# inktime.net
KiCad netlist of a schematic drawn in EAGLE
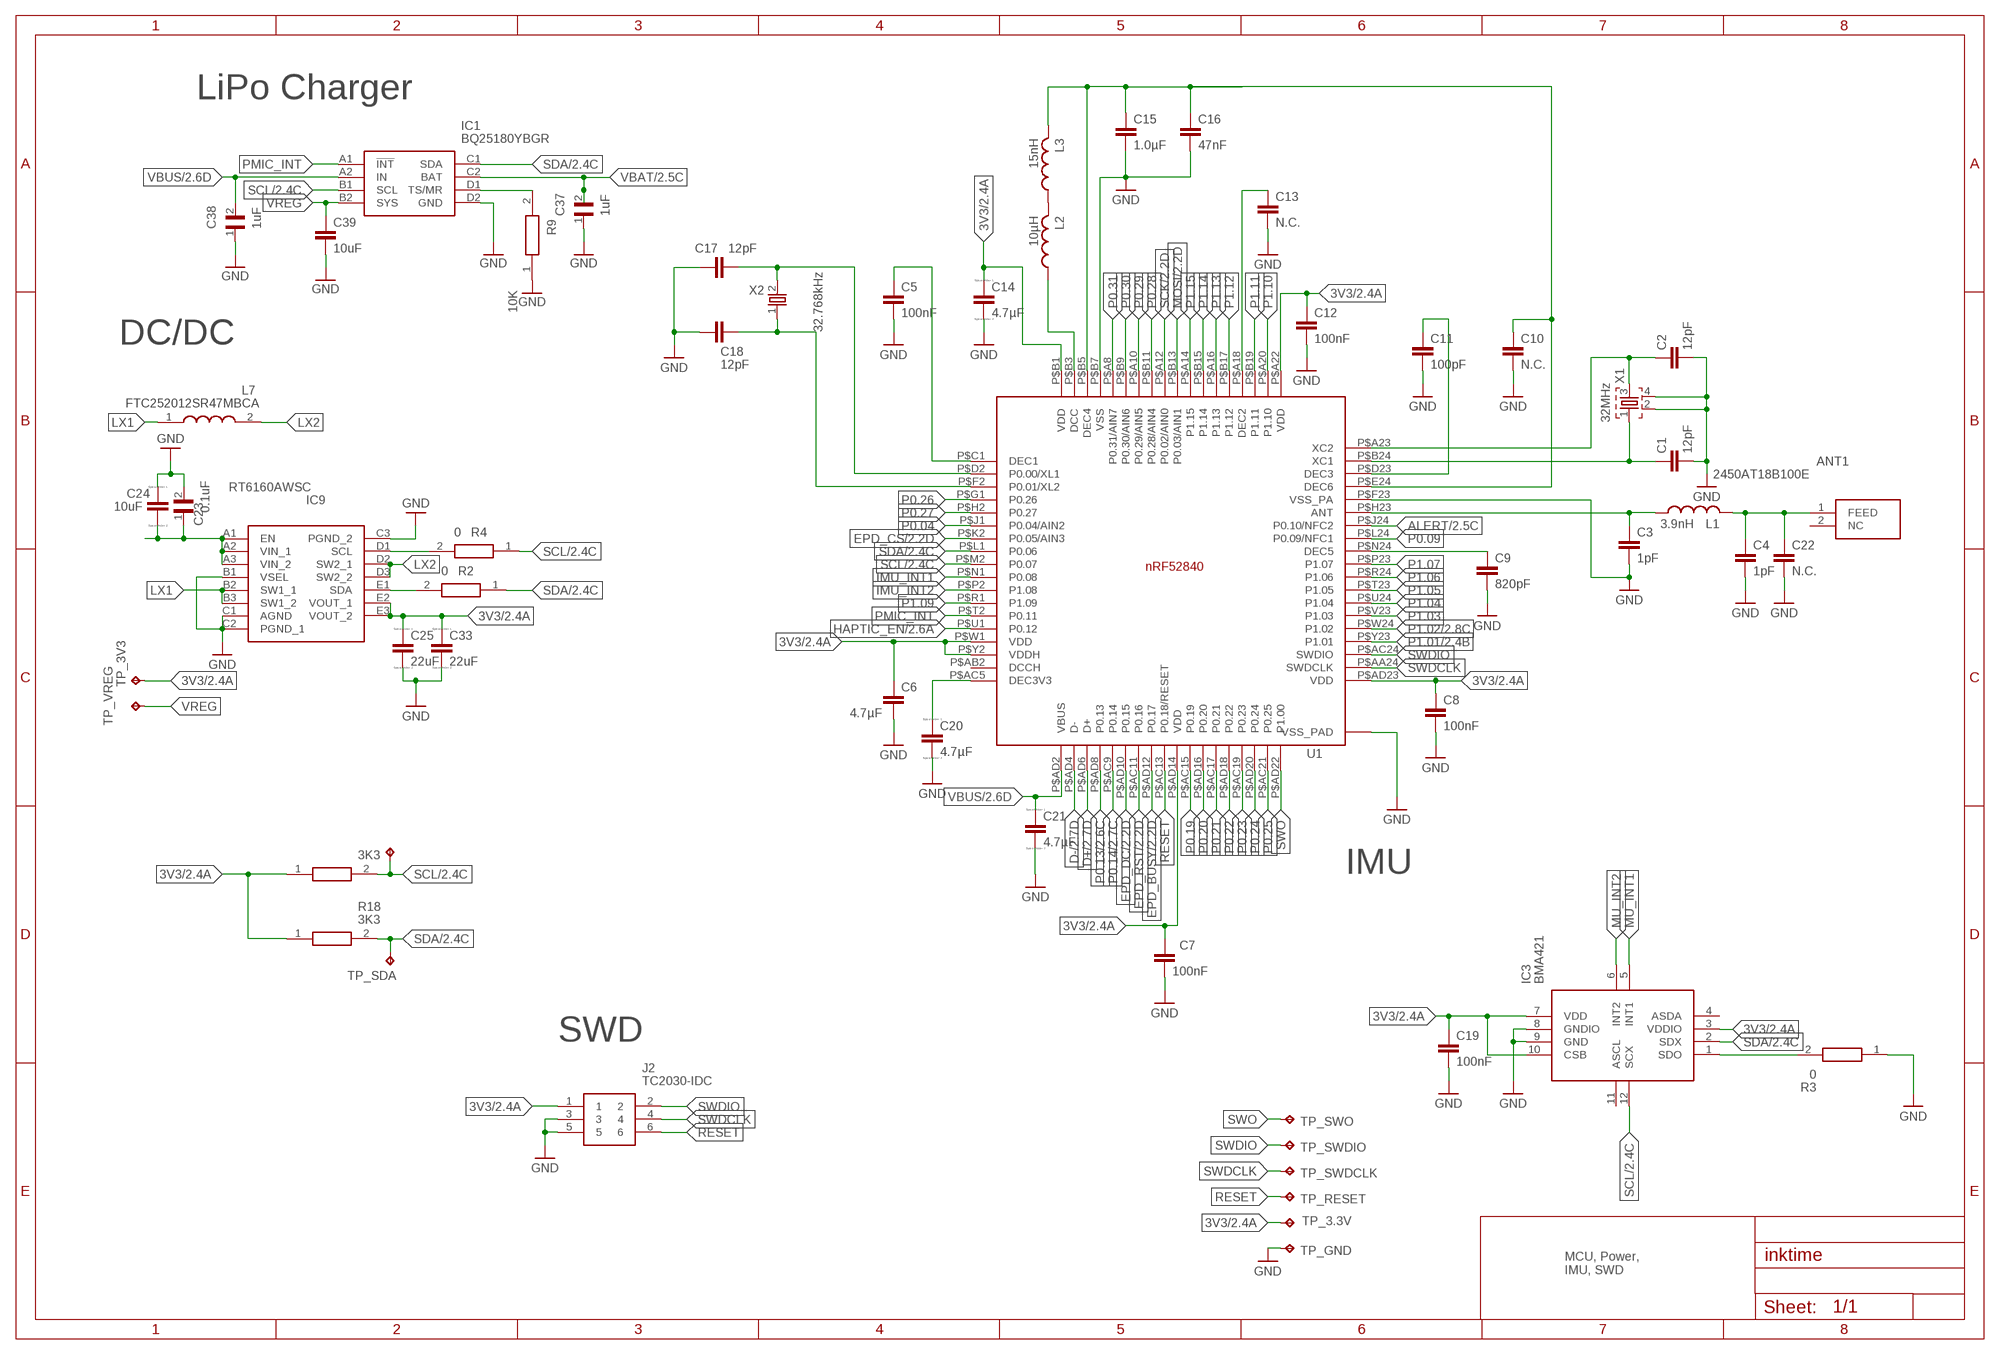
[diagram p0: schematic, sheet 1, part 1 of 2]
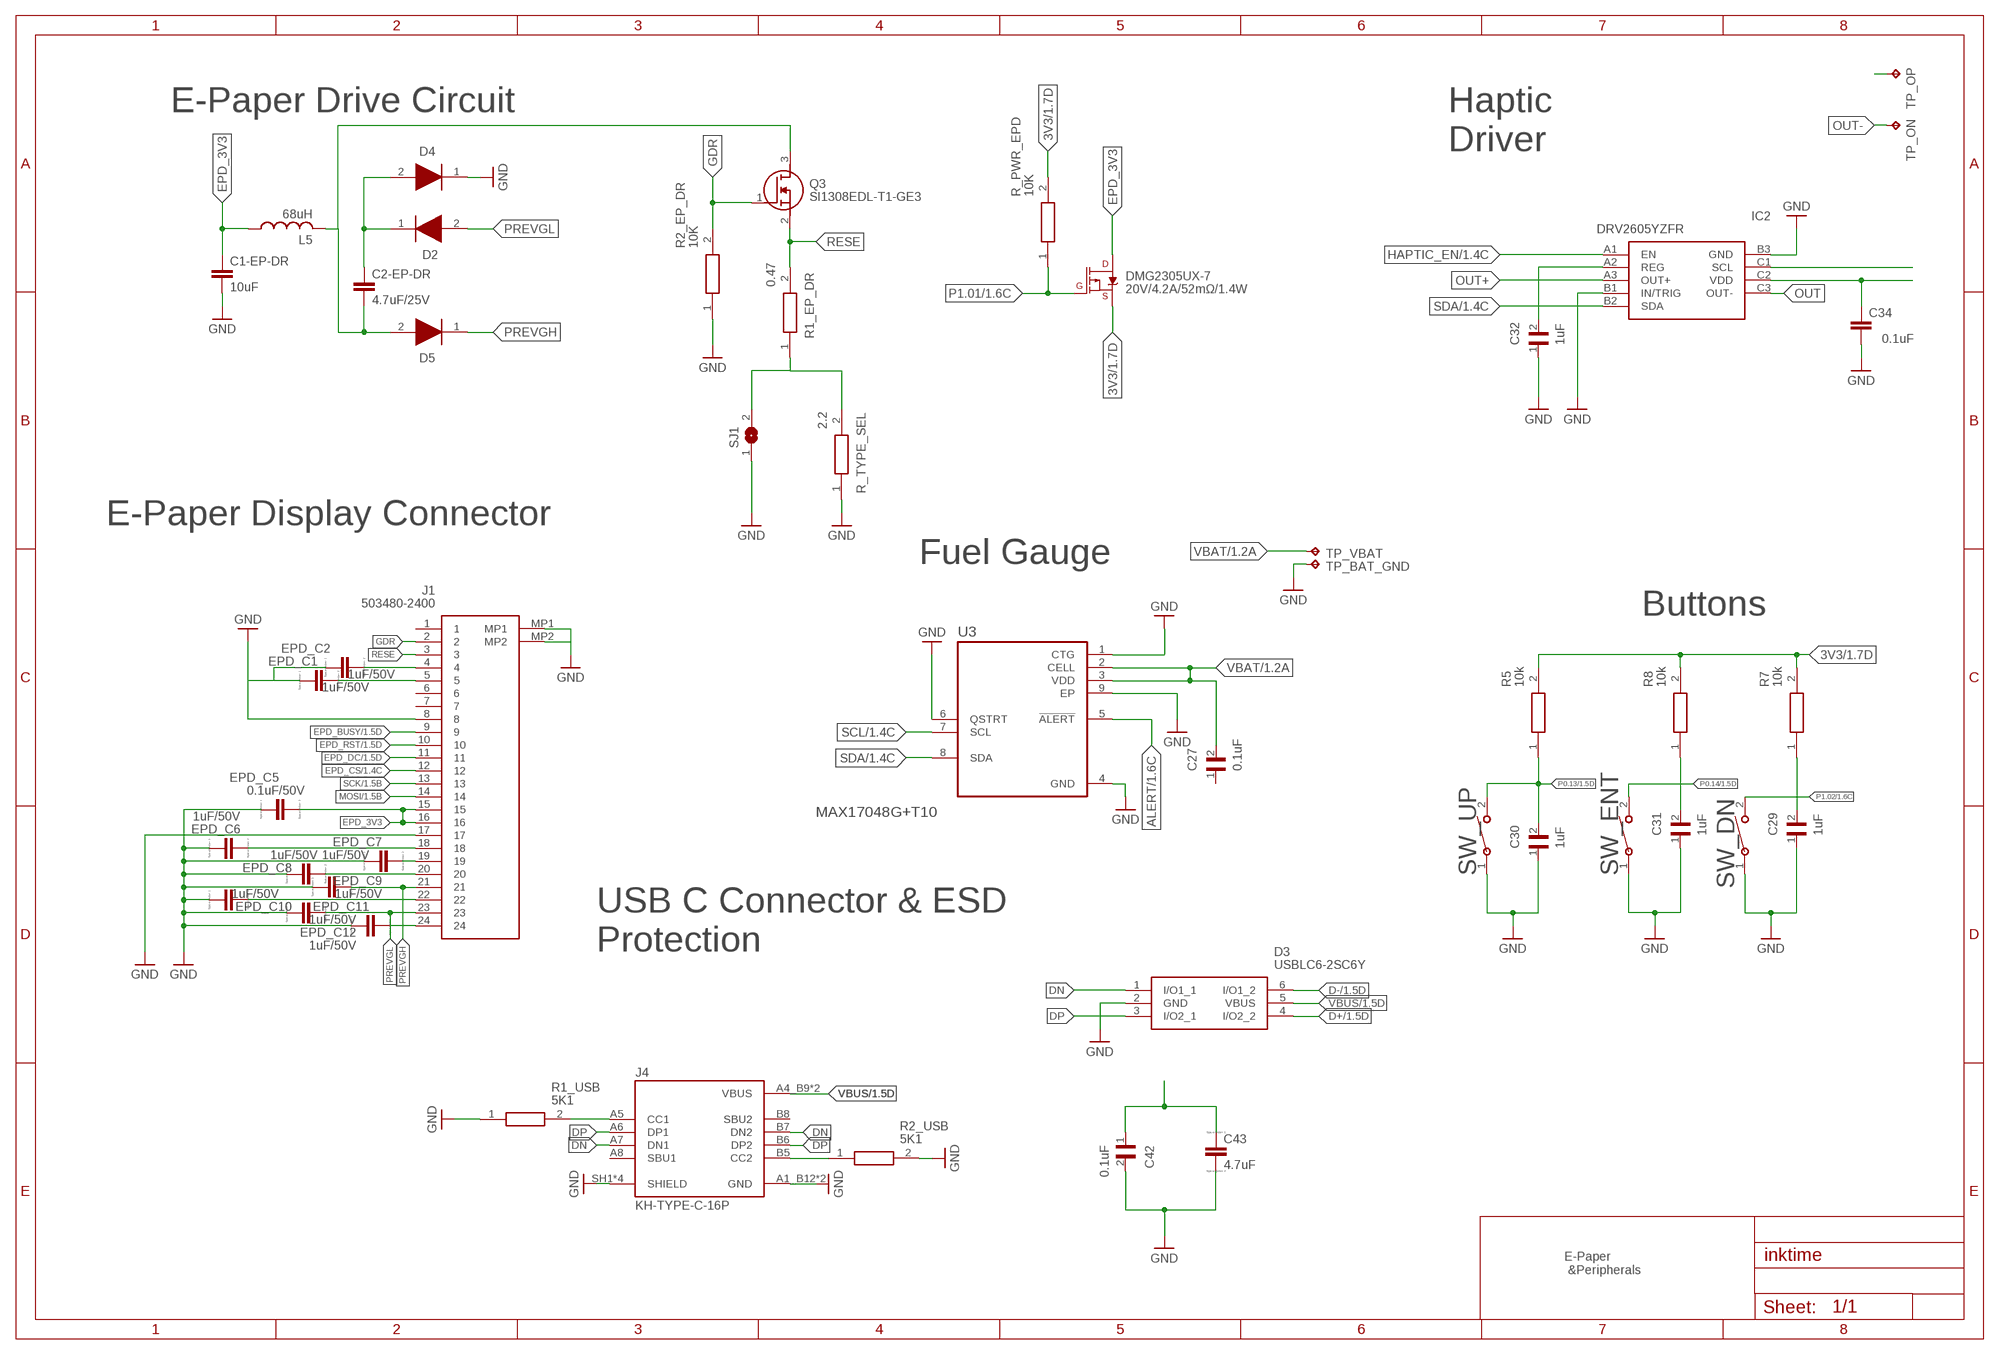
[diagram p1: schematic, sheet 1, part 2 of 2]

(export (version "E")
  (design (tool "Eeschema 10.0.6"))
  (components
    (comp (ref "ANT1")
      (value "2450AT18B100E")
      (footprint "eagle-import:2450AT18B100E_ANTC3216X140N")
      (fields (field (name "MOUSER_PART_NUMBER") "609-2450AT18B100E"))
      (libsource (lib "eagle-import") (part "2450AT18B100E_2450AT18B100E"))
    )
    (comp (ref "C1")
      (value "12pF")
      (footprint "eagle-import:NORDIC_NRF_3_RESC0201_L")
      (libsource (lib "eagle-import") (part "NORDIC_NRF_3_CAPACITOR_0201_L"))
    )
    (comp (ref "C1-EP-DR")
      (value "10uF")
      (footprint "eagle-import:NORDIC_NRF_3_RESC0201_L")
      (libsource (lib "eagle-import") (part "NORDIC_NRF_3_CAPACITOR_0201_L"))
    )
    (comp (ref "C2")
      (value "12pF")
      (footprint "eagle-import:NORDIC_NRF_3_RESC0201_L")
      (libsource (lib "eagle-import") (part "NORDIC_NRF_3_CAPACITOR_0201_L"))
    )
    (comp (ref "C2-EP-DR")
      (value "4.7uF/25V")
      (footprint "eagle-import:NORDIC_NRF_3_RESC0201_L")
      (libsource (lib "eagle-import") (part "NORDIC_NRF_3_CAPACITOR_0201_L"))
    )
    (comp (ref "C3")
      (value "1pF")
      (footprint "eagle-import:NORDIC_NRF_3_RESC0201_L")
      (libsource (lib "eagle-import") (part "NORDIC_NRF_3_CAPACITOR_0201_L"))
    )
    (comp (ref "C4")
      (value "1pF")
      (footprint "eagle-import:NORDIC_NRF_3_RESC0201_L")
      (libsource (lib "eagle-import") (part "NORDIC_NRF_3_CAPACITOR_0201_L"))
    )
    (comp (ref "C5")
      (value "100nF")
      (footprint "eagle-import:NORDIC_NRF_3_RESC0201_L")
      (libsource (lib "eagle-import") (part "NORDIC_NRF_3_CAPACITOR_0201_L"))
    )
    (comp (ref "C6")
      (value "4.7µF")
      (footprint "eagle-import:NORDIC_NRF_3_RESC0201_L")
      (libsource (lib "eagle-import") (part "NORDIC_NRF_3_CAPACITOR_0201_L"))
    )
    (comp (ref "C7")
      (value "100nF")
      (footprint "eagle-import:NORDIC_NRF_3_RESC0201_L")
      (libsource (lib "eagle-import") (part "NORDIC_NRF_3_CAPACITOR_0201_L"))
    )
    (comp (ref "C8")
      (value "100nF")
      (footprint "eagle-import:NORDIC_NRF_3_RESC0201_L")
      (libsource (lib "eagle-import") (part "NORDIC_NRF_3_CAPACITOR_0201_L"))
    )
    (comp (ref "C9")
      (value "820pF")
      (footprint "eagle-import:NORDIC_NRF_3_RESC0201_L")
      (libsource (lib "eagle-import") (part "NORDIC_NRF_3_CAPACITOR_0201_L"))
    )
    (comp (ref "C10")
      (value "N.C.")
      (footprint "eagle-import:NORDIC_NRF_3_RESC0201_L")
      (libsource (lib "eagle-import") (part "NORDIC_NRF_3_CAPACITOR_0201_L"))
    )
    (comp (ref "C11")
      (value "100pF")
      (footprint "eagle-import:NORDIC_NRF_3_RESC0201_L")
      (libsource (lib "eagle-import") (part "NORDIC_NRF_3_CAPACITOR_0201_L"))
    )
    (comp (ref "C12")
      (value "100nF")
      (footprint "eagle-import:NORDIC_NRF_3_RESC0201_L")
      (libsource (lib "eagle-import") (part "NORDIC_NRF_3_CAPACITOR_0201_L"))
    )
    (comp (ref "C13")
      (value "N.C.")
      (footprint "eagle-import:NORDIC_NRF_3_RESC0201_L")
      (libsource (lib "eagle-import") (part "NORDIC_NRF_3_CAPACITOR_0201_L"))
    )
    (comp (ref "C14")
      (value "4.7µF")
      (footprint "eagle-import:ESP32_C6_LIBRARY_1_ESP32_WROVER_EAGLE-LTSPICE_C0402")
      (libsource (lib "eagle-import") (part "ESP32_C6_LIBRARY_1_ESP32_WROVER_EAGLE-LTSPICE_CC0402"))
    )
    (comp (ref "C15")
      (value "1.0µF")
      (footprint "eagle-import:NORDIC_NRF_3_RESC0201_L")
      (libsource (lib "eagle-import") (part "NORDIC_NRF_3_CAPACITOR_0201_L"))
    )
    (comp (ref "C16")
      (value "47nF")
      (footprint "eagle-import:NORDIC_NRF_3_RESC0201_L")
      (libsource (lib "eagle-import") (part "NORDIC_NRF_3_CAPACITOR_0201_L"))
    )
    (comp (ref "C17")
      (value "12pF")
      (footprint "eagle-import:NORDIC_NRF_3_RESC0201_L")
      (libsource (lib "eagle-import") (part "NORDIC_NRF_3_CAPACITOR_0201_L"))
    )
    (comp (ref "C18")
      (value "12pF")
      (footprint "eagle-import:NORDIC_NRF_3_RESC0201_L")
      (libsource (lib "eagle-import") (part "NORDIC_NRF_3_CAPACITOR_0201_L"))
    )
    (comp (ref "C19")
      (value "100nF")
      (footprint "eagle-import:NORDIC_NRF_3_RESC0201_L")
      (libsource (lib "eagle-import") (part "NORDIC_NRF_3_CAPACITOR_0201_L"))
    )
    (comp (ref "C20")
      (value "4.7µF")
      (footprint "eagle-import:ESP32_C6_LIBRARY_1_ESP32_WROVER_EAGLE-LTSPICE_C0402")
      (libsource (lib "eagle-import") (part "ESP32_C6_LIBRARY_1_ESP32_WROVER_EAGLE-LTSPICE_CC0402"))
    )
    (comp (ref "C21")
      (value "4.7µF")
      (footprint "eagle-import:ESP32_C6_LIBRARY_1_ESP32_WROVER_EAGLE-LTSPICE_C0402")
      (libsource (lib "eagle-import") (part "ESP32_C6_LIBRARY_1_ESP32_WROVER_EAGLE-LTSPICE_CC0402"))
    )
    (comp (ref "C22")
      (value "N.C.")
      (footprint "eagle-import:NORDIC_NRF_3_RESC0201_L")
      (libsource (lib "eagle-import") (part "NORDIC_NRF_3_CAPACITOR_0201_L"))
    )
    (comp (ref "C23")
      (value "0.1uF")
      (footprint "eagle-import:GRM011R60J152KE01L_2_CAPC0201X13N")
      (fields (field (name "MF") "Murata") (field (name "MP") "GRM011R60J152KE01L"))
      (libsource (lib "eagle-import") (part "GRM011R60J152KE01L_2_GRM011R60J152KE01L"))
    )
    (comp (ref "C24")
      (value "10uF")
      (footprint "eagle-import:ESP32_C6_LIBRARY_1_ESP32_WROVER_EAGLE-LTSPICE_C0402")
      (libsource (lib "eagle-import") (part "ESP32_C6_LIBRARY_1_ESP32_WROVER_EAGLE-LTSPICE_CC0402"))
    )
    (comp (ref "C25")
      (value "22uF")
      (footprint "eagle-import:ESP32_C6_LIBRARY_1_ESP32_WROVER_EAGLE-LTSPICE_C0402")
      (libsource (lib "eagle-import") (part "ESP32_C6_LIBRARY_1_ESP32_WROVER_EAGLE-LTSPICE_CC0402"))
    )
    (comp (ref "C27")
      (value "0.1uF")
      (footprint "eagle-import:GRM011R60J152KE01L_2_CAPC0201X13N")
      (fields (field (name "MF") "Murata") (field (name "MP") "GRM011R60J152KE01L"))
      (libsource (lib "eagle-import") (part "GRM011R60J152KE01L_2_GRM011R60J152KE01L"))
    )
    (comp (ref "C29")
      (value "1uF")
      (footprint "eagle-import:GRM011R60J152KE01L_2_CAPC0201X13N")
      (fields (field (name "MF") "Murata") (field (name "MP") "GRM011R60J152KE01L"))
      (libsource (lib "eagle-import") (part "GRM011R60J152KE01L_2_GRM011R60J152KE01L"))
    )
    (comp (ref "C30")
      (value "1uF")
      (footprint "eagle-import:GRM011R60J152KE01L_2_CAPC0201X13N")
      (fields (field (name "MF") "Murata") (field (name "MP") "GRM011R60J152KE01L"))
      (libsource (lib "eagle-import") (part "GRM011R60J152KE01L_2_GRM011R60J152KE01L"))
    )
    (comp (ref "C31")
      (value "1uF")
      (footprint "eagle-import:GRM011R60J152KE01L_2_CAPC0201X13N")
      (fields (field (name "MF") "Murata") (field (name "MP") "GRM011R60J152KE01L"))
      (libsource (lib "eagle-import") (part "GRM011R60J152KE01L_2_GRM011R60J152KE01L"))
    )
    (comp (ref "C32")
      (value "1uF")
      (footprint "eagle-import:GRM011R60J152KE01L_2_CAPC0201X13N")
      (fields (field (name "MF") "Murata") (field (name "MP") "GRM011R60J152KE01L"))
      (libsource (lib "eagle-import") (part "GRM011R60J152KE01L_2_GRM011R60J152KE01L"))
    )
    (comp (ref "C33")
      (value "22uF")
      (footprint "eagle-import:ESP32_C6_LIBRARY_1_ESP32_WROVER_EAGLE-LTSPICE_C0402")
      (libsource (lib "eagle-import") (part "ESP32_C6_LIBRARY_1_ESP32_WROVER_EAGLE-LTSPICE_CC0402"))
    )
    (comp (ref "C34")
      (value "0.1uF")
      (footprint "eagle-import:NORDIC_NRF_3_RESC0201_L")
      (libsource (lib "eagle-import") (part "NORDIC_NRF_3_CAPACITOR_0201_L"))
    )
    (comp (ref "C37")
      (value "1uF")
      (footprint "eagle-import:GRM011R60J152KE01L_2_CAPC0201X13N")
      (fields (field (name "MF") "Murata") (field (name "MP") "GRM011R60J152KE01L"))
      (libsource (lib "eagle-import") (part "GRM011R60J152KE01L_2_GRM011R60J152KE01L"))
    )
    (comp (ref "C38")
      (value "1uF")
      (footprint "eagle-import:GRM011R60J152KE01L_2_CAPC0201X13N")
      (fields (field (name "MF") "Murata") (field (name "MP") "GRM011R60J152KE01L"))
      (libsource (lib "eagle-import") (part "GRM011R60J152KE01L_2_GRM011R60J152KE01L"))
    )
    (comp (ref "C39")
      (value "10uF")
      (footprint "eagle-import:NORDIC_NRF_3_RESC0201_L")
      (libsource (lib "eagle-import") (part "NORDIC_NRF_3_CAPACITOR_0201_L"))
    )
    (comp (ref "C42")
      (value "0.1uF")
      (footprint "eagle-import:GRM011R60J152KE01L_2_CAPC0201X13N")
      (fields (field (name "MF") "Murata") (field (name "MP") "GRM011R60J152KE01L"))
      (libsource (lib "eagle-import") (part "GRM011R60J152KE01L_2_GRM011R60J152KE01L"))
    )
    (comp (ref "C43")
      (value "4.7uF")
      (footprint "eagle-import:ESP32_C6_LIBRARY_1_ESP32_WROVER_EAGLE-LTSPICE_C0402")
      (libsource (lib "eagle-import") (part "ESP32_C6_LIBRARY_1_ESP32_WROVER_EAGLE-LTSPICE_CC0402"))
    )
    (comp (ref "D2")
      (value "ESP32_C6_LIBRARY_5_MBR0530")
      (footprint "eagle-import:ESP32_C6_LIBRARY_5_SOD3716X135N")
      (fields (field (name "MF") "ON Semiconductor") (field (name "MP") "MBR0530"))
      (libsource (lib "eagle-import") (part "ESP32_C6_LIBRARY_5_MBR0530"))
    )
    (comp (ref "D3")
      (value "USBLC6-2SC6Y")
      (footprint "eagle-import:ESP32_C6_LIBRARY_3_SOT95P280X145-6N")
      (fields (field (name "MF") "STMicroelectronics"))
      (libsource (lib "eagle-import") (part "ESP32_C6_LIBRARY_3_USBLC6-2SC6Y"))
    )
    (comp (ref "D4")
      (value "ESP32_C6_LIBRARY_5_MBR0530")
      (footprint "eagle-import:ESP32_C6_LIBRARY_5_SOD3716X135N")
      (fields (field (name "MF") "ON Semiconductor") (field (name "MP") "MBR0530"))
      (libsource (lib "eagle-import") (part "ESP32_C6_LIBRARY_5_MBR0530"))
    )
    (comp (ref "D5")
      (value "ESP32_C6_LIBRARY_5_MBR0530")
      (footprint "eagle-import:ESP32_C6_LIBRARY_5_SOD3716X135N")
      (fields (field (name "MF") "ON Semiconductor") (field (name "MP") "MBR0530"))
      (libsource (lib "eagle-import") (part "ESP32_C6_LIBRARY_5_MBR0530"))
    )
    (comp (ref "DMG2305UX-7")
      (value "20V/4.2A/52mΩ/1.4W")
      (footprint "eagle-import:ESP32_C6_LIBRARY_4_ESP32_C6_LIBRARY_4_ESP32_C6_LIBRARY_4_ESP32_C6_LIBRARY_4_ESP32_WROVER_SPARKFUN-DISCRETESEMI_SOT23-3")
      (libsource (lib "eagle-import") (part "ESP32_C6_LIBRARY_4_ESP32_WROVER_SPARKFUN-DISCRETESEMI_MOSFET_PCH-DMG2305UX-7"))
    )
    (comp (ref "EPD_C1")
      (value "1uF/50V")
      (footprint "eagle-import:ESP32_C6_LIBRARY_1_ESP32_WROVER_EAGLE-LTSPICE_C0402")
      (libsource (lib "eagle-import") (part "ESP32_C6_LIBRARY_1_ESP32_WROVER_EAGLE-LTSPICE_CC0402"))
    )
    (comp (ref "EPD_C2")
      (value "1uF/50V")
      (footprint "eagle-import:ESP32_C6_LIBRARY_1_ESP32_WROVER_EAGLE-LTSPICE_C0402")
      (libsource (lib "eagle-import") (part "ESP32_C6_LIBRARY_1_ESP32_WROVER_EAGLE-LTSPICE_CC0402"))
    )
    (comp (ref "EPD_C5")
      (value "0.1uF/50V")
      (footprint "eagle-import:ESP32_C6_LIBRARY_1_ESP32_WROVER_EAGLE-LTSPICE_C0402")
      (libsource (lib "eagle-import") (part "ESP32_C6_LIBRARY_1_ESP32_WROVER_EAGLE-LTSPICE_CC0402"))
    )
    (comp (ref "EPD_C6")
      (value "1uF/50V")
      (footprint "eagle-import:ESP32_C6_LIBRARY_1_ESP32_WROVER_EAGLE-LTSPICE_C0402")
      (libsource (lib "eagle-import") (part "ESP32_C6_LIBRARY_1_ESP32_WROVER_EAGLE-LTSPICE_CC0402"))
    )
    (comp (ref "EPD_C7")
      (value "1uF/50V")
      (footprint "eagle-import:ESP32_C6_LIBRARY_1_ESP32_WROVER_EAGLE-LTSPICE_C0402")
      (libsource (lib "eagle-import") (part "ESP32_C6_LIBRARY_1_ESP32_WROVER_EAGLE-LTSPICE_CC0402"))
    )
    (comp (ref "EPD_C8")
      (value "1uF/50V")
      (footprint "eagle-import:ESP32_C6_LIBRARY_1_ESP32_WROVER_EAGLE-LTSPICE_C0402")
      (libsource (lib "eagle-import") (part "ESP32_C6_LIBRARY_1_ESP32_WROVER_EAGLE-LTSPICE_CC0402"))
    )
    (comp (ref "EPD_C9")
      (value "1uF/50V")
      (footprint "eagle-import:ESP32_C6_LIBRARY_1_ESP32_WROVER_EAGLE-LTSPICE_C0402")
      (libsource (lib "eagle-import") (part "ESP32_C6_LIBRARY_1_ESP32_WROVER_EAGLE-LTSPICE_CC0402"))
    )
    (comp (ref "EPD_C10")
      (value "1uF/50V")
      (footprint "eagle-import:ESP32_C6_LIBRARY_1_ESP32_WROVER_EAGLE-LTSPICE_C0402")
      (libsource (lib "eagle-import") (part "ESP32_C6_LIBRARY_1_ESP32_WROVER_EAGLE-LTSPICE_CC0402"))
    )
    (comp (ref "EPD_C11")
      (value "1uF/50V")
      (footprint "eagle-import:ESP32_C6_LIBRARY_1_ESP32_WROVER_EAGLE-LTSPICE_C0402")
      (libsource (lib "eagle-import") (part "ESP32_C6_LIBRARY_1_ESP32_WROVER_EAGLE-LTSPICE_CC0402"))
    )
    (comp (ref "EPD_C12")
      (value "1uF/50V")
      (footprint "eagle-import:ESP32_C6_LIBRARY_1_ESP32_WROVER_EAGLE-LTSPICE_C0402")
      (libsource (lib "eagle-import") (part "ESP32_C6_LIBRARY_1_ESP32_WROVER_EAGLE-LTSPICE_CC0402"))
    )
    (comp (ref "IC1")
      (value "BQ25180YBGR")
      (footprint "eagle-import:BQ25180YBGR_BGA8C40P2X4_100X155X50")
      (fields (field (name "MOUSER_PART_NUMBER") "595-BQ25180YBGR"))
      (libsource (lib "eagle-import") (part "BQ25180YBGR_BQ25180YBGR"))
    )
    (comp (ref "IC2")
      (value "DRV2605YZFR")
      (footprint "eagle-import:DRV2605YZFR_BGA9C50P3X3_144X144X62")
      (libsource (lib "eagle-import") (part "DRV2605YZFR_DRV2605YZFR"))
    )
    (comp (ref "IC3")
      (value "BMA421")
      (footprint "eagle-import:BMA423_BMA423")
      (fields (field (name "ARROW_PART_NUMBER") "BMA423") (field (name "MOUSER_PART_NUMBER") "262-BMA423"))
      (libsource (lib "eagle-import") (part "BMA423_BMA423"))
    )
    (comp (ref "IC9")
      (value "RT6160AWSC")
      (footprint "eagle-import:RT6160AWSC_BGA15C40P3X5_140X230X60")
      (fields (field (name "MOUSER_PART_NUMBER") "835-RT6160AWSC"))
      (libsource (lib "eagle-import") (part "RT6160AWSC_RT6160AWSC"))
    )
    (comp (ref "J1")
      (value "503480-2400")
      (footprint "eagle-import:503480-2400_5034802400")
      (fields (field (name "MOUSER_PART_NUMBER") "538-503480-2400"))
      (libsource (lib "eagle-import") (part "503480-2400_503480-2400"))
    )
    (comp (ref "J2")
      (value "TC2030-IDC")
      (footprint "eagle-import:TC2030-IDC_TC2030IDC")
      (libsource (lib "eagle-import") (part "TC2030-IDC_TC2030-IDC"))
    )
    (comp (ref "J4")
      (value "KH-TYPE-C-16P")
      (footprint "eagle-import:KH-TYPE-C-16P_KINGHELM_KH-TYPE-C-16P")
      (fields (field (name "MF") "kinghelm"))
      (libsource (lib "eagle-import") (part "KH-TYPE-C-16P_KH-TYPE-C-16P"))
    )
    (comp (ref "L1")
      (value "3.9nH")
      (footprint "eagle-import:NORDIC_NRF_2_RESC0402_L")
      (libsource (lib "eagle-import") (part "NORDIC_NRF_2_INDUCTOR_0402_L"))
    )
    (comp (ref "L2")
      (value "10µH")
      (footprint "eagle-import:NORDIC_NRF_2_RESC0402_L")
      (libsource (lib "eagle-import") (part "NORDIC_NRF_2_INDUCTOR_0402_L"))
    )
    (comp (ref "L3")
      (value "15nH")
      (footprint "eagle-import:NORDIC_NRF_2_RESC0402_L")
      (libsource (lib "eagle-import") (part "NORDIC_NRF_2_INDUCTOR_0402_L"))
    )
    (comp (ref "L5")
      (value "68uH")
      (footprint "eagle-import:NORDIC_NRF_2_RESC0402_L")
      (libsource (lib "eagle-import") (part "NORDIC_NRF_2_INDUCTOR_0402_L"))
    )
    (comp (ref "L7")
      (value "FTC252012SR47MBCA")
      (footprint "eagle-import:MLP2016SR47MT0S1_INDC2016X100N")
      (libsource (lib "eagle-import") (part "MLP2016SR47MT0S1_FTC252012SR47MBCA"))
    )
    (comp (ref "Q3")
      (value "SI1308EDL-T1-GE3")
      (footprint "eagle-import:ESP32_C6_LIBRARY_6_SOT65P210X110-3N")
      (fields (field (name "MF") "Vishay Siliconix"))
      (libsource (lib "eagle-import") (part "ESP32_C6_LIBRARY_6_SI1308EDL-T1-GE3"))
    )
    (comp (ref "R1_EP_DR")
      (value "0.47")
      (footprint "eagle-import:ERA-1AEB3401C_0201")
      (libsource (lib "eagle-import") (part "ERA-1AEB3401C_CPF0201D7K68C1"))
    )
    (comp (ref "R1_USB")
      (value "5K1")
      (footprint "eagle-import:CPF0201D7K68C1_0201")
      (libsource (lib "eagle-import") (part "CPF0201D7K68C1_CPF0201D7K68C1"))
    )
    (comp (ref "R2")
      (value "0")
      (footprint "eagle-import:CPF0201D7K68C1_0201")
      (libsource (lib "eagle-import") (part "CPF0201D7K68C1_CPF0201D7K68C1"))
    )
    (comp (ref "R2_EP_DR")
      (value "10K")
      (footprint "eagle-import:ERA-1AEB3401C_0201")
      (libsource (lib "eagle-import") (part "ERA-1AEB3401C_CPF0201D7K68C1"))
    )
    (comp (ref "R2_USB")
      (value "5K1")
      (footprint "eagle-import:ERA-1AEB3401C_0201")
      (libsource (lib "eagle-import") (part "ERA-1AEB3401C_CPF0201D7K68C1"))
    )
    (comp (ref "R3")
      (value "0")
      (footprint "eagle-import:ERA-1AEB3401C_0201")
      (libsource (lib "eagle-import") (part "ERA-1AEB3401C_CPF0201D7K68C1"))
    )
    (comp (ref "R4")
      (value "0")
      (footprint "eagle-import:CPF0201D7K68C1_0201")
      (libsource (lib "eagle-import") (part "CPF0201D7K68C1_CPF0201D7K68C1"))
    )
    (comp (ref "R5")
      (value "10k")
      (footprint "eagle-import:CPF0201D7K68C1_0201")
      (libsource (lib "eagle-import") (part "CPF0201D7K68C1_CPF0201D7K68C1"))
    )
    (comp (ref "R7")
      (value "10k")
      (footprint "eagle-import:CPF0201D7K68C1_0201")
      (libsource (lib "eagle-import") (part "CPF0201D7K68C1_CPF0201D7K68C1"))
    )
    (comp (ref "R8")
      (value "10k")
      (footprint "eagle-import:CPF0201D7K68C1_0201")
      (libsource (lib "eagle-import") (part "CPF0201D7K68C1_CPF0201D7K68C1"))
    )
    (comp (ref "R9")
      (value "10K")
      (footprint "eagle-import:ERA-1AEB3401C_0201")
      (libsource (lib "eagle-import") (part "ERA-1AEB3401C_CPF0201D7K68C1"))
    )
    (comp (ref "R17")
      (value "3K3")
      (footprint "eagle-import:CPF0201D7K68C1_0201")
      (libsource (lib "eagle-import") (part "CPF0201D7K68C1_CPF0201D7K68C1"))
    )
    (comp (ref "R18")
      (value "3K3")
      (footprint "eagle-import:CPF0201D7K68C1_0201")
      (libsource (lib "eagle-import") (part "CPF0201D7K68C1_CPF0201D7K68C1"))
    )
    (comp (ref "R_PWR_EPD")
      (value "10K")
      (footprint "eagle-import:CPF0201D7K68C1_0201")
      (libsource (lib "eagle-import") (part "CPF0201D7K68C1_CPF0201D7K68C1"))
    )
    (comp (ref "R_TYPE_SEL")
      (value "2.2")
      (footprint "eagle-import:ERA-1AEB3401C_0201")
      (libsource (lib "eagle-import") (part "ERA-1AEB3401C_CPF0201D7K68C1"))
    )
    (comp (ref "SJ1")
      (value "ESP32_C6_LIBRARY_7_JUMPER_SJ")
      (footprint "eagle-import:ESP32_C6_LIBRARY_7_JUMPER_SJ")
      (libsource (lib "eagle-import") (part "ESP32_C6_LIBRARY_7_JUMPER_SJ"))
    )
    (comp (ref "SW_DN")
      (value "2025-10-22_07-23-44_LIBRARY_EVP-AKE31ASW_EVP-AKE31A_PAN")
      (footprint "eagle-import:2025-10-22_07-23-44_LIBRARY_SW_EVP-AKE31A_PAN")
      (fields
        (field (name "MANUFACTURER_PART_NUMBER") "EVP-AKE31A")
        (field (name "COPYRIGHT") "Copyright (C) 2025 Ultra Librarian. All rights reserved.")
      )
      (libsource (lib "eagle-import") (part "2025-10-22_07-23-44_LIBRARY_EVP-AKE31ASW_EVP-AKE31A_PAN"))
    )
    (comp (ref "SW_ENT")
      (value "2025-10-22_07-23-44_LIBRARY_EVP-AKE31ASW_EVP-AKE31A_PAN")
      (footprint "eagle-import:2025-10-22_07-23-44_LIBRARY_SW_EVP-AKE31A_PAN")
      (fields
        (field (name "MANUFACTURER_PART_NUMBER") "EVP-AKE31A")
        (field (name "COPYRIGHT") "Copyright (C) 2025 Ultra Librarian. All rights reserved.")
      )
      (libsource (lib "eagle-import") (part "2025-10-22_07-23-44_LIBRARY_EVP-AKE31ASW_EVP-AKE31A_PAN"))
    )
    (comp (ref "SW_UP")
      (value "2025-10-22_07-23-44_LIBRARY_EVP-AKE31ASW_EVP-AKE31A_PAN")
      (footprint "eagle-import:2025-10-22_07-23-44_LIBRARY_SW_EVP-AKE31A_PAN")
      (fields
        (field (name "MANUFACTURER_PART_NUMBER") "EVP-AKE31A")
        (field (name "COPYRIGHT") "Copyright (C) 2025 Ultra Librarian. All rights reserved.")
      )
      (libsource (lib "eagle-import") (part "2025-10-22_07-23-44_LIBRARY_EVP-AKE31ASW_EVP-AKE31A_PAN"))
    )
    (comp (ref "TP_3.3V")
      (value "HECTOR_WATCH_1_TPTP20R")
      (footprint "eagle-import:HECTOR_WATCH_1_TP20R")
      (libsource (lib "eagle-import") (part "HECTOR_WATCH_1_TPTP20R"))
    )
    (comp (ref "TP_3V3")
      (value "HECTOR_WATCH_1_TPTP20R")
      (footprint "eagle-import:HECTOR_WATCH_1_TP20R")
      (libsource (lib "eagle-import") (part "HECTOR_WATCH_1_TPTP20R"))
    )
    (comp (ref "TP_BAT_GND")
      (value "HECTOR_WATCH_1_TPTP20R")
      (footprint "eagle-import:HECTOR_WATCH_1_TP20R")
      (libsource (lib "eagle-import") (part "HECTOR_WATCH_1_TPTP20R"))
    )
    (comp (ref "TP_GND")
      (value "HECTOR_WATCH_1_TPTP20R")
      (footprint "eagle-import:HECTOR_WATCH_1_TP20R")
      (libsource (lib "eagle-import") (part "HECTOR_WATCH_1_TPTP20R"))
    )
    (comp (ref "TP_ON")
      (value "HECTOR_WATCH_1_TPTP20R")
      (footprint "eagle-import:HECTOR_WATCH_1_TP20R")
      (libsource (lib "eagle-import") (part "HECTOR_WATCH_1_TPTP20R"))
    )
    (comp (ref "TP_OP")
      (value "HECTOR_WATCH_1_TPTP20R")
      (footprint "eagle-import:HECTOR_WATCH_1_TP20R")
      (libsource (lib "eagle-import") (part "HECTOR_WATCH_1_TPTP20R"))
    )
    (comp (ref "TP_RESET")
      (value "HECTOR_WATCH_1_TPTP20R")
      (footprint "eagle-import:HECTOR_WATCH_1_TP20R")
      (libsource (lib "eagle-import") (part "HECTOR_WATCH_1_TPTP20R"))
    )
    (comp (ref "TP_SCL")
      (value "HECTOR_WATCH_1_TPTP20R")
      (footprint "eagle-import:HECTOR_WATCH_1_TP20R")
      (libsource (lib "eagle-import") (part "HECTOR_WATCH_1_TPTP20R"))
    )
    (comp (ref "TP_SDA")
      (value "HECTOR_WATCH_1_TPTP20R")
      (footprint "eagle-import:HECTOR_WATCH_1_TP20R")
      (libsource (lib "eagle-import") (part "HECTOR_WATCH_1_TPTP20R"))
    )
    (comp (ref "TP_SWDCLK")
      (value "HECTOR_WATCH_1_TPTP20R")
      (footprint "eagle-import:HECTOR_WATCH_1_TP20R")
      (libsource (lib "eagle-import") (part "HECTOR_WATCH_1_TPTP20R"))
    )
    (comp (ref "TP_SWDIO")
      (value "HECTOR_WATCH_1_TPTP20R")
      (footprint "eagle-import:HECTOR_WATCH_1_TP20R")
      (libsource (lib "eagle-import") (part "HECTOR_WATCH_1_TPTP20R"))
    )
    (comp (ref "TP_SWO")
      (value "HECTOR_WATCH_1_TPTP20R")
      (footprint "eagle-import:HECTOR_WATCH_1_TP20R")
      (libsource (lib "eagle-import") (part "HECTOR_WATCH_1_TPTP20R"))
    )
    (comp (ref "TP_VBAT")
      (value "HECTOR_WATCH_1_TPTP20R")
      (footprint "eagle-import:HECTOR_WATCH_1_TP20R")
      (libsource (lib "eagle-import") (part "HECTOR_WATCH_1_TPTP20R"))
    )
    (comp (ref "TP_VREG")
      (value "HECTOR_WATCH_1_TPTP20R")
      (footprint "eagle-import:HECTOR_WATCH_1_TP20R")
      (libsource (lib "eagle-import") (part "HECTOR_WATCH_1_TPTP20R"))
    )
    (comp (ref "U1")
      (value "NRF52840_QF")
      (footprint "eagle-import:NORDIC_NRF_4_AQFN50P700X700X85_HS-74N")
      (libsource (lib "eagle-import") (part "NORDIC_NRF_4_NRF52840_QF"))
    )
    (comp (ref "U3")
      (value "MAX17048G+T10")
      (footprint "eagle-import:ESP32_C6_LIBRARY_SON50P200X200X80-9N")
      (fields (field (name "MF") "Analog Devices"))
      (libsource (lib "eagle-import") (part "ESP32_C6_LIBRARY_MAX17048G+T10"))
    )
    (comp (ref "X1")
      (value "32MHz")
      (footprint "eagle-import:NORDIC_NRF_BT-XTAL_2016_N")
      (libsource (lib "eagle-import") (part "NORDIC_NRF_XTAL_32MHZ"))
    )
    (comp (ref "X2")
      (value "32.768kHz")
      (footprint "eagle-import:NORDIC_NRF_1_XTAL_3215_N")
      (libsource (lib "eagle-import") (part "NORDIC_NRF_1_XTAL_32KHZ"))
    )
  )
  (nets
    (net (code "1") (name "3V3{slash}1.7D") (class "Default")
      (node (ref "DMG2305UX-7") (pin "2") (pinfunction "S_2") (pintype "bidirectional"))
      (node (ref "R5") (pin "2") (pinfunction "2_2") (pintype "bidirectional"))
      (node (ref "R7") (pin "2") (pinfunction "2_2") (pintype "bidirectional"))
      (node (ref "R8") (pin "2") (pinfunction "2_2") (pintype "bidirectional"))
      (node (ref "R_PWR_EPD") (pin "2") (pinfunction "2_2") (pintype "bidirectional"))
    )
    (net (code "2") (name "3V3{slash}2.4A") (class "Default")
      (node (ref "C12") (pin "1") (pinfunction "1_1") (pintype "passive"))
      (node (ref "C14") (pin "1") (pinfunction "1_1") (pintype "passive"))
      (node (ref "C19") (pin "1") (pinfunction "1_1") (pintype "passive"))
      (node (ref "C25") (pin "1") (pinfunction "1_1") (pintype "passive"))
      (node (ref "C33") (pin "1") (pinfunction "1_1") (pintype "passive"))
      (node (ref "C6") (pin "1") (pinfunction "1_1") (pintype "passive"))
      (node (ref "C7") (pin "1") (pinfunction "1_1") (pintype "passive"))
      (node (ref "C8") (pin "1") (pinfunction "1_1") (pintype "passive"))
      (node (ref "IC3") (pin "10") (pinfunction "CSB_10") (pintype "bidirectional"))
      (node (ref "IC3") (pin "3") (pinfunction "VDDIO_3") (pintype "bidirectional"))
      (node (ref "IC3") (pin "7") (pinfunction "VDD_7") (pintype "bidirectional"))
      (node (ref "IC9") (pin "E2") (pinfunction "VOUT_1_E2") (pintype "bidirectional"))
      (node (ref "IC9") (pin "E3") (pinfunction "VOUT_2_E3") (pintype "bidirectional"))
      (node (ref "J2") (pin "1") (pinfunction "1_1") (pintype "bidirectional"))
      (node (ref "R17") (pin "1") (pinfunction "1_1") (pintype "bidirectional"))
      (node (ref "R18") (pin "1") (pinfunction "1_1") (pintype "bidirectional"))
      (node (ref "TP_3.3V") (pin "TP") (pinfunction "TP_TP") (pintype "input"))
      (node (ref "TP_3V3") (pin "TP") (pinfunction "TP_TP") (pintype "input"))
      (node (ref "U1") (pin "P$A22") (pinfunction "VDD_P$A22") (pintype "power_in"))
      (node (ref "U1") (pin "P$AD14") (pinfunction "VDD_P$AD14") (pintype "power_in"))
      (node (ref "U1") (pin "P$AD23") (pinfunction "VDD_P$AD23") (pintype "power_in"))
      (node (ref "U1") (pin "P$B1") (pinfunction "VDD_P$B1") (pintype "power_in"))
      (node (ref "U1") (pin "P$W1") (pinfunction "VDD_P$W1") (pintype "power_in"))
      (node (ref "U1") (pin "P$Y2") (pinfunction "VDDH_P$Y2") (pintype "power_in"))
    )
    (net (code "3") (name "ALERT{slash}1.6C") (class "Default")
      (node (ref "U3") (pin "5") (pinfunction "~{ALERT}_5") (pintype "output"))
    )
    (net (code "4") (name "ALERT{slash}2.5C") (class "Default")
      (node (ref "U1") (pin "P$J24") (pinfunction "P0.10/NFC2_P$J24") (pintype "bidirectional"))
    )
    (net (code "5") (name "D+{slash}1.5D") (class "Default")
      (node (ref "D3") (pin "4") (pinfunction "I/O2_2_4") (pintype "bidirectional"))
    )
    (net (code "6") (name "D+{slash}2.7D") (class "Default")
      (node (ref "U1") (pin "P$AD6") (pinfunction "D+_P$AD6") (pintype "bidirectional"))
    )
    (net (code "7") (name "D-{slash}1.5D") (class "Default")
      (node (ref "D3") (pin "6") (pinfunction "I/O1_2_6") (pintype "bidirectional"))
    )
    (net (code "8") (name "D-{slash}2.7D") (class "Default")
      (node (ref "U1") (pin "P$AD4") (pinfunction "D-_P$AD4") (pintype "bidirectional"))
    )
    (net (code "9") (name "DN") (class "Default")
      (node (ref "D3") (pin "1") (pinfunction "I/O1_1_1") (pintype "bidirectional"))
      (node (ref "J4") (pin "A7") (pinfunction "DN1_A7") (pintype "bidirectional"))
      (node (ref "J4") (pin "B7") (pinfunction "DN2_B7") (pintype "bidirectional"))
    )
    (net (code "10") (name "DP") (class "Default")
      (node (ref "D3") (pin "3") (pinfunction "I/O2_1_3") (pintype "bidirectional"))
      (node (ref "J4") (pin "A6") (pinfunction "DP1_A6") (pintype "bidirectional"))
      (node (ref "J4") (pin "B6") (pinfunction "DP2_B6") (pintype "bidirectional"))
    )
    (net (code "11") (name "EPD_3V3") (class "Default")
      (node (ref "C1-EP-DR") (pin "1") (pinfunction "1_1") (pintype "passive"))
      (node (ref "DMG2305UX-7") (pin "3") (pinfunction "D_3") (pintype "bidirectional"))
      (node (ref "EPD_C5") (pin "2") (pinfunction "2_2") (pintype "passive"))
      (node (ref "J1") (pin "15") (pinfunction "15_15") (pintype "bidirectional"))
      (node (ref "J1") (pin "16") (pinfunction "16_16") (pintype "bidirectional"))
      (node (ref "L5") (pin "1") (pinfunction "1_1") (pintype "passive"))
    )
    (net (code "12") (name "EPD_BUSY{slash}1.5D") (class "Default")
      (node (ref "J1") (pin "9") (pinfunction "9_9") (pintype "bidirectional"))
    )
    (net (code "13") (name "EPD_BUSY{slash}2.2D") (class "Default")
      (node (ref "U1") (pin "P$AD12") (pinfunction "P0.17_P$AD12") (pintype "bidirectional"))
    )
    (net (code "14") (name "EPD_CS{slash}1.4C") (class "Default")
      (node (ref "J1") (pin "12") (pinfunction "12_12") (pintype "bidirectional"))
    )
    (net (code "15") (name "EPD_CS{slash}2.2D") (class "Default")
      (node (ref "U1") (pin "P$K2") (pinfunction "P0.05/AIN3_P$K2") (pintype "bidirectional"))
    )
    (net (code "16") (name "EPD_DC{slash}1.5D") (class "Default")
      (node (ref "J1") (pin "11") (pinfunction "11_11") (pintype "bidirectional"))
    )
    (net (code "17") (name "EPD_DC{slash}2.2D") (class "Default")
      (node (ref "U1") (pin "P$AD10") (pinfunction "P0.15_P$AD10") (pintype "bidirectional"))
    )
    (net (code "18") (name "EPD_RST{slash}1.5D") (class "Default")
      (node (ref "J1") (pin "10") (pinfunction "10_10") (pintype "bidirectional"))
    )
    (net (code "19") (name "EPD_RST{slash}2.2D") (class "Default")
      (node (ref "U1") (pin "P$AC11") (pinfunction "P0.16_P$AC11") (pintype "bidirectional"))
    )
    (net (code "20") (name "GDR") (class "Default")
      (node (ref "J1") (pin "2") (pinfunction "2_2") (pintype "bidirectional"))
      (node (ref "Q3") (pin "1") (pinfunction "G_1") (pintype "bidirectional"))
      (node (ref "R2_EP_DR") (pin "2") (pinfunction "2_2") (pintype "bidirectional"))
    )
    (net (code "21") (name "GND") (class "Default")
      (node (ref "C1") (pin "2") (pinfunction "2_2") (pintype "passive"))
      (node (ref "C1-EP-DR") (pin "2") (pinfunction "2_2") (pintype "passive"))
      (node (ref "C10") (pin "2") (pinfunction "2_2") (pintype "passive"))
      (node (ref "C11") (pin "2") (pinfunction "2_2") (pintype "passive"))
      (node (ref "C12") (pin "2") (pinfunction "2_2") (pintype "passive"))
      (node (ref "C13") (pin "2") (pinfunction "2_2") (pintype "passive"))
      (node (ref "C14") (pin "2") (pinfunction "2_2") (pintype "passive"))
      (node (ref "C15") (pin "2") (pinfunction "2_2") (pintype "passive"))
      (node (ref "C16") (pin "2") (pinfunction "2_2") (pintype "passive"))
      (node (ref "C17") (pin "1") (pinfunction "1_1") (pintype "passive"))
      (node (ref "C18") (pin "2") (pinfunction "2_2") (pintype "passive"))
      (node (ref "C19") (pin "2") (pinfunction "2_2") (pintype "passive"))
      (node (ref "C2") (pin "2") (pinfunction "2_2") (pintype "passive"))
      (node (ref "C20") (pin "2") (pinfunction "2_2") (pintype "passive"))
      (node (ref "C21") (pin "2") (pinfunction "2_2") (pintype "passive"))
      (node (ref "C22") (pin "2") (pinfunction "2_2") (pintype "passive"))
      (node (ref "C23") (pin "2") (pinfunction "2_2") (pintype "passive"))
      (node (ref "C24") (pin "1") (pinfunction "1_1") (pintype "passive"))
      (node (ref "C25") (pin "2") (pinfunction "2_2") (pintype "passive"))
      (node (ref "C29") (pin "1") (pinfunction "1_1") (pintype "passive"))
      (node (ref "C3") (pin "2") (pinfunction "2_2") (pintype "passive"))
      (node (ref "C30") (pin "1") (pinfunction "1_1") (pintype "passive"))
      (node (ref "C31") (pin "1") (pinfunction "1_1") (pintype "passive"))
      (node (ref "C32") (pin "1") (pinfunction "1_1") (pintype "passive"))
      (node (ref "C33") (pin "2") (pinfunction "2_2") (pintype "passive"))
      (node (ref "C34") (pin "2") (pinfunction "2_2") (pintype "passive"))
      (node (ref "C37") (pin "1") (pinfunction "1_1") (pintype "passive"))
      (node (ref "C38") (pin "1") (pinfunction "1_1") (pintype "passive"))
      (node (ref "C39") (pin "2") (pinfunction "2_2") (pintype "passive"))
      (node (ref "C4") (pin "2") (pinfunction "2_2") (pintype "passive"))
      (node (ref "C42") (pin "2") (pinfunction "2_2") (pintype "passive"))
      (node (ref "C43") (pin "2") (pinfunction "2_2") (pintype "passive"))
      (node (ref "C5") (pin "2") (pinfunction "2_2") (pintype "passive"))
      (node (ref "C6") (pin "2") (pinfunction "2_2") (pintype "passive"))
      (node (ref "C7") (pin "2") (pinfunction "2_2") (pintype "passive"))
      (node (ref "C8") (pin "2") (pinfunction "2_2") (pintype "passive"))
      (node (ref "C9") (pin "2") (pinfunction "2_2") (pintype "passive"))
      (node (ref "D3") (pin "2") (pinfunction "GND_2") (pintype "bidirectional"))
      (node (ref "D4") (pin "1") (pinfunction "K_1") (pintype "bidirectional"))
      (node (ref "EPD_C10") (pin "1") (pinfunction "1_1") (pintype "passive"))
      (node (ref "EPD_C11") (pin "1") (pinfunction "1_1") (pintype "passive"))
      (node (ref "EPD_C12") (pin "1") (pinfunction "1_1") (pintype "passive"))
      (node (ref "EPD_C5") (pin "1") (pinfunction "1_1") (pintype "passive"))
      (node (ref "EPD_C6") (pin "1") (pinfunction "1_1") (pintype "passive"))
      (node (ref "EPD_C7") (pin "1") (pinfunction "1_1") (pintype "passive"))
      (node (ref "EPD_C8") (pin "1") (pinfunction "1_1") (pintype "passive"))
      (node (ref "EPD_C9") (pin "1") (pinfunction "1_1") (pintype "passive"))
      (node (ref "IC1") (pin "D2") (pinfunction "GND_D2") (pintype "bidirectional"))
      (node (ref "IC2") (pin "B1") (pinfunction "IN/TRIG_B1") (pintype "bidirectional"))
      (node (ref "IC2") (pin "B3") (pinfunction "GND_B3") (pintype "bidirectional"))
      (node (ref "IC3") (pin "8") (pinfunction "GNDIO_8") (pintype "bidirectional"))
      (node (ref "IC3") (pin "9") (pinfunction "GND_9") (pintype "bidirectional"))
      (node (ref "IC9") (pin "B1") (pinfunction "VSEL_B1") (pintype "bidirectional"))
      (node (ref "IC9") (pin "C1") (pinfunction "AGND_C1") (pintype "bidirectional"))
      (node (ref "IC9") (pin "C2") (pinfunction "PGND_1_C2") (pintype "bidirectional"))
      (node (ref "IC9") (pin "C3") (pinfunction "PGND_2_C3") (pintype "bidirectional"))
      (node (ref "J1") (pin "17") (pinfunction "17_17") (pintype "bidirectional"))
      (node (ref "J1") (pin "8") (pinfunction "8_8") (pintype "bidirectional"))
      (node (ref "J1") (pin "MP1") (pinfunction "MP1_MP1") (pintype "bidirectional"))
      (node (ref "J2") (pin "3") (pinfunction "3_3") (pintype "bidirectional"))
      (node (ref "J2") (pin "5") (pinfunction "5_5") (pintype "bidirectional"))
      (node (ref "J4") (pin "A12_B1") (pinfunction "GND_A12_B1") (pintype "power_in"))
      (node (ref "J4") (pin "A1_B12") (pinfunction "GND_A1_B12") (pintype "power_in"))
      (node (ref "J4") (pin "SH1") (pinfunction "SHIELD_SH1") (pintype "passive"))
      (node (ref "J4") (pin "SH2") (pinfunction "SHIELD_SH2") (pintype "passive"))
      (node (ref "J4") (pin "SH3") (pinfunction "SHIELD_SH3") (pintype "passive"))
      (node (ref "J4") (pin "SH4") (pinfunction "SHIELD_SH4") (pintype "passive"))
      (node (ref "R1_USB") (pin "1") (pinfunction "1_1") (pintype "bidirectional"))
      (node (ref "R2_EP_DR") (pin "1") (pinfunction "1_1") (pintype "bidirectional"))
      (node (ref "R2_USB") (pin "2") (pinfunction "2_2") (pintype "bidirectional"))
      (node (ref "R3") (pin "1") (pinfunction "1_1") (pintype "bidirectional"))
      (node (ref "R9") (pin "1") (pinfunction "1_1") (pintype "bidirectional"))
      (node (ref "R_TYPE_SEL") (pin "1") (pinfunction "1_1") (pintype "bidirectional"))
      (node (ref "SJ1") (pin "1") (pinfunction "1_1") (pintype "passive"))
      (node (ref "SW_DN") (pin "1") (pinfunction "1_1") (pintype "passive"))
      (node (ref "SW_ENT") (pin "1") (pinfunction "1_1") (pintype "passive"))
      (node (ref "SW_UP") (pin "1") (pinfunction "1_1") (pintype "passive"))
      (node (ref "TP_BAT_GND") (pin "TP") (pinfunction "TP_TP") (pintype "input"))
      (node (ref "TP_GND") (pin "TP") (pinfunction "TP_TP") (pintype "input"))
      (node (ref "U1") (pin "P$74") (pinfunction "VSS_PAD_P$74") (pintype "bidirectional"))
      (node (ref "U1") (pin "P$75") (pinfunction "VSS_PAD_P$75") (pintype "bidirectional"))
      (node (ref "U1") (pin "P$76") (pinfunction "VSS_PAD_P$76") (pintype "bidirectional"))
      (node (ref "U1") (pin "P$77") (pinfunction "VSS_PAD_P$77") (pintype "bidirectional"))
      (node (ref "U1") (pin "P$78") (pinfunction "VSS_PAD_P$78") (pintype "bidirectional"))
      (node (ref "U1") (pin "P$79") (pinfunction "VSS_PAD_P$79") (pintype "bidirectional"))
      (node (ref "U1") (pin "P$80") (pinfunction "VSS_PAD_P$80") (pintype "bidirectional"))
      (node (ref "U1") (pin "P$81") (pinfunction "VSS_PAD_P$81") (pintype "bidirectional"))
      (node (ref "U1") (pin "P$82") (pinfunction "VSS_PAD_P$82") (pintype "bidirectional"))
      (node (ref "U1") (pin "P$83") (pinfunction "VSS_PAD_P$83") (pintype "bidirectional"))
      (node (ref "U1") (pin "P$84") (pinfunction "VSS_PAD_P$84") (pintype "bidirectional"))
      (node (ref "U1") (pin "P$85") (pinfunction "VSS_PAD_P$85") (pintype "bidirectional"))
      (node (ref "U1") (pin "P$86") (pinfunction "VSS_PAD_P$86") (pintype "bidirectional"))
      (node (ref "U1") (pin "P$87") (pinfunction "VSS_PAD_P$87") (pintype "bidirectional"))
      (node (ref "U1") (pin "P$88") (pinfunction "VSS_PAD_P$88") (pintype "bidirectional"))
      (node (ref "U1") (pin "P$89") (pinfunction "VSS_PAD_P$89") (pintype "bidirectional"))
      (node (ref "U1") (pin "P$90") (pinfunction "VSS_PAD_P$90") (pintype "bidirectional"))
      (node (ref "U1") (pin "P$B7") (pinfunction "VSS_P$B7") (pintype "power_in"))
      (node (ref "U1") (pin "P$F23") (pinfunction "VSS_PA_P$F23") (pintype "bidirectional"))
      (node (ref "U3") (pin "1") (pinfunction "CTG_1") (pintype "power_in"))
      (node (ref "U3") (pin "4") (pinfunction "GND_4") (pintype "power_in"))
      (node (ref "U3") (pin "6") (pinfunction "QSTRT_6") (pintype "input"))
      (node (ref "U3") (pin "9") (pinfunction "EP_9") (pintype "power_in"))
      (node (ref "X1") (pin "2") (pinfunction "2_2") (pintype "passive"))
      (node (ref "X1") (pin "4") (pinfunction "4_4") (pintype "passive"))
    )
    (net (code "22") (name "HAPTIC_EN{slash}1.4C") (class "Default")
      (node (ref "IC2") (pin "A1") (pinfunction "EN_A1") (pintype "bidirectional"))
    )
    (net (code "23") (name "HAPTIC_EN{slash}2.6A") (class "Default")
      (node (ref "U1") (pin "P$U1") (pinfunction "P0.12_P$U1") (pintype "bidirectional"))
    )
    (net (code "24") (name "IMU_INT1") (class "Default")
      (node (ref "U1") (pin "P$N1") (pinfunction "P0.08_P$N1") (pintype "bidirectional"))
    )
    (net (code "25") (name "IMU_INT2") (class "Default")
      (node (ref "U1") (pin "P$P2") (pinfunction "P1.08_P$P2") (pintype "bidirectional"))
    )
    (net (code "26") (name "LX1") (class "Default")
      (node (ref "IC9") (pin "B2") (pinfunction "SW1_1_B2") (pintype "bidirectional"))
      (node (ref "IC9") (pin "B3") (pinfunction "SW1_2_B3") (pintype "bidirectional"))
      (node (ref "L7") (pin "1") (pinfunction "1_1") (pintype "bidirectional"))
    )
    (net (code "27") (name "LX2") (class "Default")
      (node (ref "IC9") (pin "D2") (pinfunction "SW2_1_D2") (pintype "bidirectional"))
      (node (ref "IC9") (pin "D3") (pinfunction "SW2_2_D3") (pintype "bidirectional"))
      (node (ref "L7") (pin "2") (pinfunction "2_2") (pintype "bidirectional"))
    )
    (net (code "28") (name "MOSI{slash}1.5B") (class "Default")
      (node (ref "J1") (pin "14") (pinfunction "14_14") (pintype "bidirectional"))
    )
    (net (code "29") (name "MOSI{slash}2.2D") (class "Default")
      (node (ref "U1") (pin "P$B13") (pinfunction "P0.03/AIN1_P$B13") (pintype "bidirectional"))
    )
    (net (code "30") (name "MU_INT1") (class "Default")
      (node (ref "IC3") (pin "5") (pinfunction "INT1_5") (pintype "bidirectional"))
    )
    (net (code "31") (name "MU_INT2") (class "Default")
      (node (ref "IC3") (pin "6") (pinfunction "INT2_6") (pintype "bidirectional"))
    )
    (net (code "32") (name "Net-(ANT1-FEED)") (class "Default")
      (node (ref "ANT1") (pin "1") (pinfunction "FEED_1") (pintype "input"))
      (node (ref "C22") (pin "1") (pinfunction "1_1") (pintype "passive"))
      (node (ref "C4") (pin "1") (pinfunction "1_1") (pintype "passive"))
      (node (ref "L1") (pin "2") (pinfunction "2_2") (pintype "passive"))
    )
    (net (code "33") (name "Net-(C29-Pad2)") (class "Default")
      (node (ref "C29") (pin "2") (pinfunction "2_2") (pintype "passive"))
      (node (ref "R7") (pin "1") (pinfunction "1_1") (pintype "bidirectional"))
    )
    (net (code "34") (name "Net-(C31-Pad2)") (class "Default")
      (node (ref "C31") (pin "2") (pinfunction "2_2") (pintype "passive"))
      (node (ref "R8") (pin "1") (pinfunction "1_1") (pintype "bidirectional"))
    )
    (net (code "35") (name "Net-(C42-Pad1)") (class "Default")
      (node (ref "C42") (pin "1") (pinfunction "1_1") (pintype "passive"))
      (node (ref "C43") (pin "1") (pinfunction "1_1") (pintype "passive"))
    )
    (net (code "36") (name "Net-(D2-K)") (class "Default")
      (node (ref "C2-EP-DR") (pin "1") (pinfunction "1_1") (pintype "passive"))
      (node (ref "D2") (pin "1") (pinfunction "K_1") (pintype "bidirectional"))
      (node (ref "D4") (pin "2") (pinfunction "A_2") (pintype "bidirectional"))
    )
    (net (code "37") (name "Net-(D5-A)") (class "Default")
      (node (ref "C2-EP-DR") (pin "2") (pinfunction "2_2") (pintype "passive"))
      (node (ref "D5") (pin "2") (pinfunction "A_2") (pintype "bidirectional"))
      (node (ref "L5") (pin "2") (pinfunction "2_2") (pintype "passive"))
      (node (ref "Q3") (pin "3") (pinfunction "D_3") (pintype "bidirectional"))
    )
    (net (code "38") (name "Net-(EPD_C1-Pad2)") (class "Default")
      (node (ref "EPD_C1") (pin "2") (pinfunction "2_2") (pintype "passive"))
      (node (ref "J1") (pin "5") (pinfunction "5_5") (pintype "bidirectional"))
    )
    (net (code "39") (name "Net-(EPD_C2-Pad2)") (class "Default")
      (node (ref "EPD_C2") (pin "2") (pinfunction "2_2") (pintype "passive"))
      (node (ref "J1") (pin "4") (pinfunction "4_4") (pintype "bidirectional"))
    )
    (net (code "40") (name "Net-(EPD_C6-Pad2)") (class "Default")
      (node (ref "EPD_C6") (pin "2") (pinfunction "2_2") (pintype "passive"))
      (node (ref "J1") (pin "18") (pinfunction "18_18") (pintype "bidirectional"))
    )
    (net (code "41") (name "Net-(EPD_C7-Pad2)") (class "Default")
      (node (ref "EPD_C7") (pin "2") (pinfunction "2_2") (pintype "passive"))
      (node (ref "J1") (pin "19") (pinfunction "19_19") (pintype "bidirectional"))
    )
    (net (code "42") (name "Net-(EPD_C8-Pad2)") (class "Default")
      (node (ref "EPD_C8") (pin "2") (pinfunction "2_2") (pintype "passive"))
      (node (ref "J1") (pin "20") (pinfunction "20_20") (pintype "bidirectional"))
    )
    (net (code "43") (name "Net-(EPD_C10-Pad2)") (class "Default")
      (node (ref "EPD_C10") (pin "2") (pinfunction "2_2") (pintype "passive"))
      (node (ref "J1") (pin "22") (pinfunction "22_22") (pintype "bidirectional"))
    )
    (net (code "44") (name "Net-(EPD_C12-Pad2)") (class "Default")
      (node (ref "EPD_C12") (pin "2") (pinfunction "2_2") (pintype "passive"))
      (node (ref "J1") (pin "24") (pinfunction "24_24") (pintype "bidirectional"))
    )
    (net (code "45") (name "Net-(IC1-TS{slash}MR)") (class "Default")
      (node (ref "IC1") (pin "D1") (pinfunction "TS/MR_D1") (pintype "bidirectional"))
      (node (ref "R9") (pin "2") (pinfunction "2_2") (pintype "bidirectional"))
    )
    (net (code "46") (name "Net-(IC2-REG)") (class "Default")
      (node (ref "C32") (pin "2") (pinfunction "2_2") (pintype "passive"))
      (node (ref "IC2") (pin "A2") (pinfunction "REG_A2") (pintype "bidirectional"))
    )
    (net (code "47") (name "Net-(IC2-VDD)") (class "Default")
      (node (ref "C34") (pin "1") (pinfunction "1_1") (pintype "passive"))
      (node (ref "IC2") (pin "C2") (pinfunction "VDD_C2") (pintype "bidirectional"))
    )
    (net (code "48") (name "Net-(IC3-SDO)") (class "Default")
      (node (ref "IC3") (pin "1") (pinfunction "SDO_1") (pintype "bidirectional"))
      (node (ref "R3") (pin "2") (pinfunction "2_2") (pintype "bidirectional"))
    )
    (net (code "49") (name "Net-(IC9-SCL)") (class "Default")
      (node (ref "IC9") (pin "D1") (pinfunction "SCL_D1") (pintype "bidirectional"))
      (node (ref "R4") (pin "2") (pinfunction "2_2") (pintype "bidirectional"))
    )
    (net (code "50") (name "Net-(IC9-SDA)") (class "Default")
      (node (ref "IC9") (pin "E1") (pinfunction "SDA_E1") (pintype "bidirectional"))
      (node (ref "R2") (pin "2") (pinfunction "2_2") (pintype "bidirectional"))
    )
    (net (code "51") (name "Net-(J4-CC1)") (class "Default")
      (node (ref "J4") (pin "A5") (pinfunction "CC1_A5") (pintype "bidirectional"))
      (node (ref "R1_USB") (pin "2") (pinfunction "2_2") (pintype "bidirectional"))
    )
    (net (code "52") (name "Net-(J4-CC2)") (class "Default")
      (node (ref "J4") (pin "B5") (pinfunction "CC2_B5") (pintype "bidirectional"))
      (node (ref "R2_USB") (pin "1") (pinfunction "1_1") (pintype "bidirectional"))
    )
    (net (code "53") (name "Net-(L2-Pad2)") (class "Default")
      (node (ref "L2") (pin "2") (pinfunction "2_2") (pintype "passive"))
      (node (ref "L3") (pin "1") (pinfunction "1_1") (pintype "passive"))
    )
    (net (code "54") (name "Net-(R1_EP_DR-Pad1)") (class "Default")
      (node (ref "R1_EP_DR") (pin "1") (pinfunction "1_1") (pintype "bidirectional"))
      (node (ref "R_TYPE_SEL") (pin "2") (pinfunction "2_2") (pintype "bidirectional"))
      (node (ref "SJ1") (pin "2") (pinfunction "2_2") (pintype "passive"))
    )
    (net (code "55") (name "Net-(U1-ANT)") (class "Default")
      (node (ref "C3") (pin "1") (pinfunction "1_1") (pintype "passive"))
      (node (ref "L1") (pin "1") (pinfunction "1_1") (pintype "passive"))
      (node (ref "U1") (pin "P$H23") (pinfunction "ANT_P$H23") (pintype "bidirectional"))
    )
    (net (code "56") (name "Net-(U1-DCC)") (class "Default")
      (node (ref "L2") (pin "1") (pinfunction "1_1") (pintype "passive"))
      (node (ref "U1") (pin "P$B3") (pinfunction "DCC_P$B3") (pintype "output"))
    )
    (net (code "57") (name "Net-(U1-DEC1)") (class "Default")
      (node (ref "C5") (pin "1") (pinfunction "1_1") (pintype "passive"))
      (node (ref "U1") (pin "P$C1") (pinfunction "DEC1_P$C1") (pintype "power_in"))
    )
    (net (code "58") (name "Net-(U1-DEC2)") (class "Default")
      (node (ref "C13") (pin "1") (pinfunction "1_1") (pintype "passive"))
      (node (ref "U1") (pin "P$A18") (pinfunction "DEC2_P$A18") (pintype "bidirectional"))
    )
    (net (code "59") (name "Net-(U1-DEC3)") (class "Default")
      (node (ref "C11") (pin "1") (pinfunction "1_1") (pintype "passive"))
      (node (ref "U1") (pin "P$D23") (pinfunction "DEC3_P$D23") (pintype "bidirectional"))
    )
    (net (code "60") (name "Net-(U1-DEC3V3)") (class "Default")
      (node (ref "C20") (pin "1") (pinfunction "1_1") (pintype "passive"))
      (node (ref "U1") (pin "P$AC5") (pinfunction "DEC3V3_P$AC5") (pintype "bidirectional"))
    )
    (net (code "61") (name "Net-(U1-DEC4)") (class "Default")
      (node (ref "C10") (pin "1") (pinfunction "1_1") (pintype "passive"))
      (node (ref "C15") (pin "1") (pinfunction "1_1") (pintype "passive"))
      (node (ref "C16") (pin "1") (pinfunction "1_1") (pintype "passive"))
      (node (ref "L3") (pin "2") (pinfunction "2_2") (pintype "passive"))
      (node (ref "U1") (pin "P$B5") (pinfunction "DEC4_P$B5") (pintype "power_in"))
      (node (ref "U1") (pin "P$E24") (pinfunction "DEC6_P$E24") (pintype "bidirectional"))
    )
    (net (code "62") (name "Net-(U1-DEC5)") (class "Default")
      (node (ref "C9") (pin "1") (pinfunction "1_1") (pintype "passive"))
      (node (ref "U1") (pin "P$N24") (pinfunction "DEC5_P$N24") (pintype "bidirectional"))
    )
    (net (code "63") (name "Net-(U1-P0.00{slash}XL1)") (class "Default")
      (node (ref "C17") (pin "2") (pinfunction "2_2") (pintype "passive"))
      (node (ref "U1") (pin "P$D2") (pinfunction "P0.00/XL1_P$D2") (pintype "bidirectional"))
      (node (ref "X2") (pin "2") (pinfunction "2_2") (pintype "passive"))
    )
    (net (code "64") (name "Net-(U1-P0.01{slash}XL2)") (class "Default")
      (node (ref "C18") (pin "1") (pinfunction "1_1") (pintype "passive"))
      (node (ref "U1") (pin "P$F2") (pinfunction "P0.01/XL2_P$F2") (pintype "bidirectional"))
      (node (ref "X2") (pin "1") (pinfunction "1_1") (pintype "passive"))
    )
    (net (code "65") (name "Net-(U1-XC1)") (class "Default")
      (node (ref "C1") (pin "1") (pinfunction "1_1") (pintype "passive"))
      (node (ref "U1") (pin "P$B24") (pinfunction "XC1_P$B24") (pintype "input"))
      (node (ref "X1") (pin "1") (pinfunction "1_1") (pintype "passive"))
    )
    (net (code "66") (name "Net-(U1-XC2)") (class "Default")
      (node (ref "C2") (pin "1") (pinfunction "1_1") (pintype "passive"))
      (node (ref "U1") (pin "P$A23") (pinfunction "XC2_P$A23") (pintype "output"))
      (node (ref "X1") (pin "3") (pinfunction "3_3") (pintype "passive"))
    )
    (net (code "67") (name "OUT") (class "Default")
      (node (ref "IC2") (pin "C3") (pinfunction "OUT-_C3") (pintype "bidirectional"))
    )
    (net (code "68") (name "OUT+") (class "Default")
      (node (ref "IC2") (pin "A3") (pinfunction "OUT+_A3") (pintype "bidirectional"))
      (node (ref "TP_OP") (pin "TP") (pinfunction "TP_TP") (pintype "input"))
    )
    (net (code "69") (name "OUT-") (class "Default")
      (node (ref "TP_ON") (pin "TP") (pinfunction "TP_TP") (pintype "input"))
    )
    (net (code "70") (name "P0.04") (class "Default")
      (node (ref "U1") (pin "P$J1") (pinfunction "P0.04/AIN2_P$J1") (pintype "bidirectional"))
    )
    (net (code "71") (name "P0.09") (class "Default")
      (node (ref "U1") (pin "P$L24") (pinfunction "P0.09/NFC1_P$L24") (pintype "bidirectional"))
    )
    (net (code "72") (name "P0.13{slash}1.5D") (class "Default")
      (node (ref "C30") (pin "2") (pinfunction "2_2") (pintype "passive"))
      (node (ref "R5") (pin "1") (pinfunction "1_1") (pintype "bidirectional"))
      (node (ref "SW_UP") (pin "2") (pinfunction "2_2") (pintype "passive"))
    )
    (net (code "73") (name "P0.13{slash}2.6C") (class "Default")
      (node (ref "U1") (pin "P$AD8") (pinfunction "P0.13_P$AD8") (pintype "bidirectional"))
    )
    (net (code "74") (name "P0.14{slash}1.5D") (class "Default")
      (node (ref "SW_ENT") (pin "2") (pinfunction "2_2") (pintype "passive"))
    )
    (net (code "75") (name "P0.14{slash}2.7C") (class "Default")
      (node (ref "U1") (pin "P$AC9") (pinfunction "P0.14_P$AC9") (pintype "bidirectional"))
    )
    (net (code "76") (name "P0.19") (class "Default")
      (node (ref "U1") (pin "P$AC15") (pinfunction "P0.19_P$AC15") (pintype "bidirectional"))
    )
    (net (code "77") (name "P0.20") (class "Default")
      (node (ref "U1") (pin "P$AD16") (pinfunction "P0.20_P$AD16") (pintype "bidirectional"))
    )
    (net (code "78") (name "P0.21") (class "Default")
      (node (ref "U1") (pin "P$AC17") (pinfunction "P0.21_P$AC17") (pintype "bidirectional"))
    )
    (net (code "79") (name "P0.22") (class "Default")
      (node (ref "U1") (pin "P$AD18") (pinfunction "P0.22_P$AD18") (pintype "bidirectional"))
    )
    (net (code "80") (name "P0.23") (class "Default")
      (node (ref "U1") (pin "P$AC19") (pinfunction "P0.23_P$AC19") (pintype "bidirectional"))
    )
    (net (code "81") (name "P0.24") (class "Default")
      (node (ref "U1") (pin "P$AD20") (pinfunction "P0.24_P$AD20") (pintype "bidirectional"))
    )
    (net (code "82") (name "P0.25") (class "Default")
      (node (ref "U1") (pin "P$AC21") (pinfunction "P0.25_P$AC21") (pintype "bidirectional"))
    )
    (net (code "83") (name "P0.26") (class "Default")
      (node (ref "U1") (pin "P$G1") (pinfunction "P0.26_P$G1") (pintype "bidirectional"))
    )
    (net (code "84") (name "P0.27") (class "Default")
      (node (ref "U1") (pin "P$H2") (pinfunction "P0.27_P$H2") (pintype "bidirectional"))
    )
    (net (code "85") (name "P0.28") (class "Default")
      (node (ref "U1") (pin "P$B11") (pinfunction "P0.28/AIN4_P$B11") (pintype "bidirectional"))
    )
    (net (code "86") (name "P0.29") (class "Default")
      (node (ref "U1") (pin "P$A10") (pinfunction "P0.29/AIN5_P$A10") (pintype "bidirectional"))
    )
    (net (code "87") (name "P0.30") (class "Default")
      (node (ref "U1") (pin "P$B9") (pinfunction "P0.30/AIN6_P$B9") (pintype "bidirectional"))
    )
    (net (code "88") (name "P0.31") (class "Default")
      (node (ref "U1") (pin "P$A8") (pinfunction "P0.31/AIN7_P$A8") (pintype "bidirectional"))
    )
    (net (code "89") (name "P1.01{slash}1.6C") (class "Default")
      (node (ref "DMG2305UX-7") (pin "1") (pinfunction "G_1") (pintype "bidirectional"))
      (node (ref "R_PWR_EPD") (pin "1") (pinfunction "1_1") (pintype "bidirectional"))
    )
    (net (code "90") (name "P1.01{slash}2.4B") (class "Default")
      (node (ref "U1") (pin "P$Y23") (pinfunction "P1.01_P$Y23") (pintype "bidirectional"))
    )
    (net (code "91") (name "P1.02{slash}1.6C") (class "Default")
      (node (ref "SW_DN") (pin "2") (pinfunction "2_2") (pintype "passive"))
    )
    (net (code "92") (name "P1.02{slash}2.8C") (class "Default")
      (node (ref "U1") (pin "P$W24") (pinfunction "P1.02_P$W24") (pintype "bidirectional"))
    )
    (net (code "93") (name "P1.03") (class "Default")
      (node (ref "U1") (pin "P$V23") (pinfunction "P1.03_P$V23") (pintype "bidirectional"))
    )
    (net (code "94") (name "P1.04") (class "Default")
      (node (ref "U1") (pin "P$U24") (pinfunction "P1.04_P$U24") (pintype "bidirectional"))
    )
    (net (code "95") (name "P1.05") (class "Default")
      (node (ref "U1") (pin "P$T23") (pinfunction "P1.05_P$T23") (pintype "bidirectional"))
    )
    (net (code "96") (name "P1.06") (class "Default")
      (node (ref "U1") (pin "P$R24") (pinfunction "P1.06_P$R24") (pintype "bidirectional"))
    )
    (net (code "97") (name "P1.07") (class "Default")
      (node (ref "U1") (pin "P$P23") (pinfunction "P1.07_P$P23") (pintype "bidirectional"))
    )
    (net (code "98") (name "P1.09") (class "Default")
      (node (ref "U1") (pin "P$R1") (pinfunction "P1.09_P$R1") (pintype "bidirectional"))
    )
    (net (code "99") (name "P1.10") (class "Default")
      (node (ref "U1") (pin "P$A20") (pinfunction "P1.10_P$A20") (pintype "bidirectional"))
    )
    (net (code "100") (name "P1.11") (class "Default")
      (node (ref "U1") (pin "P$B19") (pinfunction "P1.11_P$B19") (pintype "bidirectional"))
    )
    (net (code "101") (name "P1.12") (class "Default")
      (node (ref "U1") (pin "P$B17") (pinfunction "P1.12_P$B17") (pintype "bidirectional"))
    )
    (net (code "102") (name "P1.13") (class "Default")
      (node (ref "U1") (pin "P$A16") (pinfunction "P1.13_P$A16") (pintype "bidirectional"))
    )
    (net (code "103") (name "P1.14") (class "Default")
      (node (ref "U1") (pin "P$B15") (pinfunction "P1.14_P$B15") (pintype "bidirectional"))
    )
    (net (code "104") (name "P1.15") (class "Default")
      (node (ref "U1") (pin "P$A14") (pinfunction "P1.15_P$A14") (pintype "bidirectional"))
    )
    (net (code "105") (name "PMIC_INT") (class "Default")
      (node (ref "IC1") (pin "A1") (pinfunction "~{INT}_A1") (pintype "bidirectional"))
      (node (ref "U1") (pin "P$T2") (pinfunction "P0.11_P$T2") (pintype "bidirectional"))
    )
    (net (code "106") (name "PREVGH") (class "Default")
      (node (ref "D5") (pin "1") (pinfunction "K_1") (pintype "bidirectional"))
      (node (ref "EPD_C9") (pin "2") (pinfunction "2_2") (pintype "passive"))
      (node (ref "J1") (pin "21") (pinfunction "21_21") (pintype "bidirectional"))
    )
    (net (code "107") (name "PREVGL") (class "Default")
      (node (ref "D2") (pin "2") (pinfunction "A_2") (pintype "bidirectional"))
      (node (ref "EPD_C11") (pin "2") (pinfunction "2_2") (pintype "passive"))
      (node (ref "J1") (pin "23") (pinfunction "23_23") (pintype "bidirectional"))
    )
    (net (code "108") (name "RESE") (class "Default")
      (node (ref "J1") (pin "3") (pinfunction "3_3") (pintype "bidirectional"))
      (node (ref "Q3") (pin "2") (pinfunction "S_2") (pintype "bidirectional"))
      (node (ref "R1_EP_DR") (pin "2") (pinfunction "2_2") (pintype "bidirectional"))
    )
    (net (code "109") (name "RESET") (class "Default")
      (node (ref "J2") (pin "6") (pinfunction "6_6") (pintype "bidirectional"))
      (node (ref "TP_RESET") (pin "TP") (pinfunction "TP_TP") (pintype "input"))
      (node (ref "U1") (pin "P$AC13") (pinfunction "P0.18/RESET_P$AC13") (pintype "bidirectional"))
    )
    (net (code "110") (name "SCK{slash}1.5B") (class "Default")
      (node (ref "J1") (pin "13") (pinfunction "13_13") (pintype "bidirectional"))
    )
    (net (code "111") (name "SCK{slash}2.2D") (class "Default")
      (node (ref "U1") (pin "P$A12") (pinfunction "P0.02/AIN0_P$A12") (pintype "bidirectional"))
    )
    (net (code "112") (name "SCL{slash}1.4C") (class "Default")
      (node (ref "U3") (pin "7") (pinfunction "SCL_7") (pintype "input"))
    )
    (net (code "113") (name "SCL{slash}2.4C") (class "Default")
      (node (ref "IC1") (pin "B1") (pinfunction "SCL_B1") (pintype "bidirectional"))
      (node (ref "IC3") (pin "12") (pinfunction "SCX_12") (pintype "bidirectional"))
      (node (ref "R17") (pin "2") (pinfunction "2_2") (pintype "bidirectional"))
      (node (ref "R4") (pin "1") (pinfunction "1_1") (pintype "bidirectional"))
      (node (ref "TP_SCL") (pin "TP") (pinfunction "TP_TP") (pintype "input"))
      (node (ref "U1") (pin "P$M2") (pinfunction "P0.07_P$M2") (pintype "bidirectional"))
    )
    (net (code "114") (name "SDA{slash}1.4C") (class "Default")
      (node (ref "IC2") (pin "B2") (pinfunction "SDA_B2") (pintype "bidirectional"))
      (node (ref "U3") (pin "8") (pinfunction "SDA_8") (pintype "bidirectional"))
    )
    (net (code "115") (name "SDA{slash}2.4C") (class "Default")
      (node (ref "IC1") (pin "C1") (pinfunction "SDA_C1") (pintype "bidirectional"))
      (node (ref "IC3") (pin "2") (pinfunction "SDX_2") (pintype "bidirectional"))
      (node (ref "R18") (pin "2") (pinfunction "2_2") (pintype "bidirectional"))
      (node (ref "R2") (pin "1") (pinfunction "1_1") (pintype "bidirectional"))
      (node (ref "TP_SDA") (pin "TP") (pinfunction "TP_TP") (pintype "input"))
      (node (ref "U1") (pin "P$L1") (pinfunction "P0.06_P$L1") (pintype "bidirectional"))
    )
    (net (code "116") (name "SWDCLK") (class "Default")
      (node (ref "J2") (pin "4") (pinfunction "4_4") (pintype "bidirectional"))
      (node (ref "TP_SWDCLK") (pin "TP") (pinfunction "TP_TP") (pintype "input"))
      (node (ref "U1") (pin "P$AA24") (pinfunction "SWDCLK_P$AA24") (pintype "input"))
    )
    (net (code "117") (name "SWDIO") (class "Default")
      (node (ref "J2") (pin "2") (pinfunction "2_2") (pintype "bidirectional"))
      (node (ref "TP_SWDIO") (pin "TP") (pinfunction "TP_TP") (pintype "input"))
      (node (ref "U1") (pin "P$AC24") (pinfunction "SWDIO_P$AC24") (pintype "bidirectional"))
    )
    (net (code "118") (name "SWO") (class "Default")
      (node (ref "TP_SWO") (pin "TP") (pinfunction "TP_TP") (pintype "input"))
      (node (ref "U1") (pin "P$AD22") (pinfunction "P1.00_P$AD22") (pintype "bidirectional"))
    )
    (net (code "119") (name "VBAT{slash}1.2A") (class "Default")
      (node (ref "C27") (pin "2") (pinfunction "2_2") (pintype "passive"))
      (node (ref "TP_VBAT") (pin "TP") (pinfunction "TP_TP") (pintype "input"))
      (node (ref "U3") (pin "2") (pinfunction "CELL_2") (pintype "power_in"))
      (node (ref "U3") (pin "3") (pinfunction "VDD_3") (pintype "power_in"))
    )
    (net (code "120") (name "VBAT{slash}2.5C") (class "Default")
      (node (ref "C37") (pin "2") (pinfunction "2_2") (pintype "passive"))
      (node (ref "IC1") (pin "C2") (pinfunction "BAT_C2") (pintype "bidirectional"))
    )
    (net (code "121") (name "VBUS{slash}1.5D") (class "Default")
      (node (ref "D3") (pin "5") (pinfunction "VBUS_5") (pintype "bidirectional"))
      (node (ref "J4") (pin "A4_B9") (pinfunction "VBUS_A4_B9") (pintype "power_in"))
      (node (ref "J4") (pin "A9_B4") (pinfunction "VBUS_A9_B4") (pintype "power_in"))
    )
    (net (code "122") (name "VBUS{slash}2.6D") (class "Default")
      (node (ref "C21") (pin "1") (pinfunction "1_1") (pintype "passive"))
      (node (ref "C38") (pin "2") (pinfunction "2_2") (pintype "passive"))
      (node (ref "IC1") (pin "A2") (pinfunction "IN_A2") (pintype "bidirectional"))
      (node (ref "U1") (pin "P$AD2") (pinfunction "VBUS_P$AD2") (pintype "power_in"))
    )
    (net (code "123") (name "VREG") (class "Default")
      (node (ref "C23") (pin "1") (pinfunction "1_1") (pintype "passive"))
      (node (ref "C24") (pin "2") (pinfunction "2_2") (pintype "passive"))
      (node (ref "C39") (pin "1") (pinfunction "1_1") (pintype "passive"))
      (node (ref "IC1") (pin "B2") (pinfunction "SYS_B2") (pintype "bidirectional"))
      (node (ref "IC9") (pin "A1") (pinfunction "EN_A1") (pintype "bidirectional"))
      (node (ref "IC9") (pin "A2") (pinfunction "VIN_1_A2") (pintype "bidirectional"))
      (node (ref "IC9") (pin "A3") (pinfunction "VIN_2_A3") (pintype "bidirectional"))
      (node (ref "TP_VREG") (pin "TP") (pinfunction "TP_TP") (pintype "input"))
    )
    (net (code "124") (name "unconnected-(ANT1-NC-Pad2)") (class "Default")
      (node (ref "ANT1") (pin "2") (pinfunction "NC_2") (pintype "no_connect"))
    )
    (net (code "125") (name "unconnected-(C27-Pad1)") (class "Default")
      (node (ref "C27") (pin "1") (pinfunction "1_1") (pintype "passive"))
    )
    (net (code "126") (name "unconnected-(EPD_C1-Pad1)") (class "Default")
      (node (ref "EPD_C1") (pin "1") (pinfunction "1_1") (pintype "passive"))
    )
    (net (code "127") (name "unconnected-(EPD_C2-Pad1)") (class "Default")
      (node (ref "EPD_C2") (pin "1") (pinfunction "1_1") (pintype "passive"))
    )
    (net (code "128") (name "unconnected-(IC2-SCL-PadC1)") (class "Default")
      (node (ref "IC2") (pin "C1") (pinfunction "SCL_C1") (pintype "bidirectional"))
    )
    (net (code "129") (name "unconnected-(IC3-ASCL-Pad11)") (class "Default")
      (node (ref "IC3") (pin "11") (pinfunction "ASCL_11") (pintype "bidirectional"))
    )
    (net (code "130") (name "unconnected-(IC3-ASDA-Pad4)") (class "Default")
      (node (ref "IC3") (pin "4") (pinfunction "ASDA_4") (pintype "bidirectional"))
    )
    (net (code "131") (name "unconnected-(J1-Pad1)") (class "Default")
      (node (ref "J1") (pin "1") (pinfunction "1_1") (pintype "bidirectional"))
    )
    (net (code "132") (name "unconnected-(J1-Pad6)") (class "Default")
      (node (ref "J1") (pin "6") (pinfunction "6_6") (pintype "bidirectional"))
    )
    (net (code "133") (name "unconnected-(J1-Pad7)") (class "Default")
      (node (ref "J1") (pin "7") (pinfunction "7_7") (pintype "bidirectional"))
    )
    (net (code "134") (name "unconnected-(J1-PadMP2)") (class "Default")
      (node (ref "J1") (pin "MP2") (pinfunction "MP2_MP2") (pintype "bidirectional"))
    )
    (net (code "135") (name "unconnected-(J4-SBU1-PadA8)") (class "Default")
      (node (ref "J4") (pin "A8") (pinfunction "SBU1_A8") (pintype "bidirectional"))
    )
    (net (code "136") (name "unconnected-(J4-SBU2-PadB8)") (class "Default")
      (node (ref "J4") (pin "B8") (pinfunction "SBU2_B8") (pintype "bidirectional"))
    )
    (net (code "137") (name "unconnected-(U1-DCCH-PadP$AB2)") (class "Default")
      (node (ref "U1") (pin "P$AB2") (pinfunction "DCCH_P$AB2") (pintype "bidirectional"))
    )
  )
)
